# main.net
KiCad netlist of a schematic drawn in EAGLE
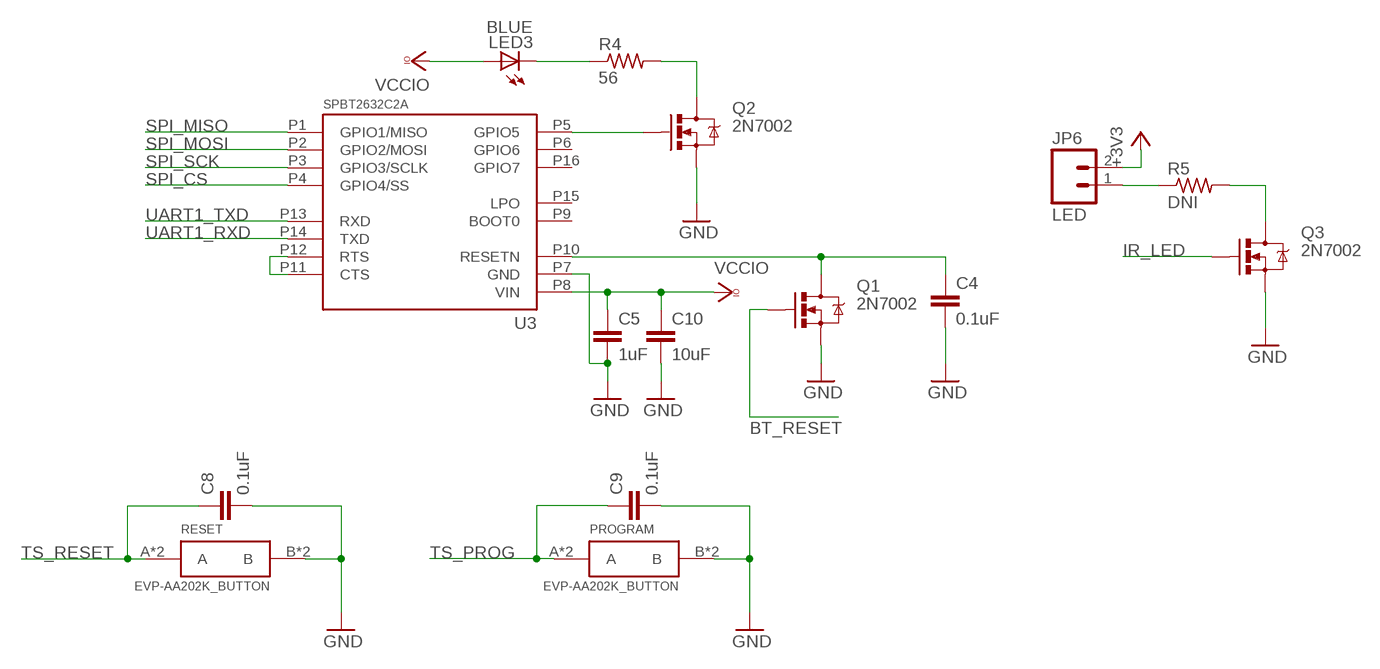
[diagram p0: schematic, sheet 1]
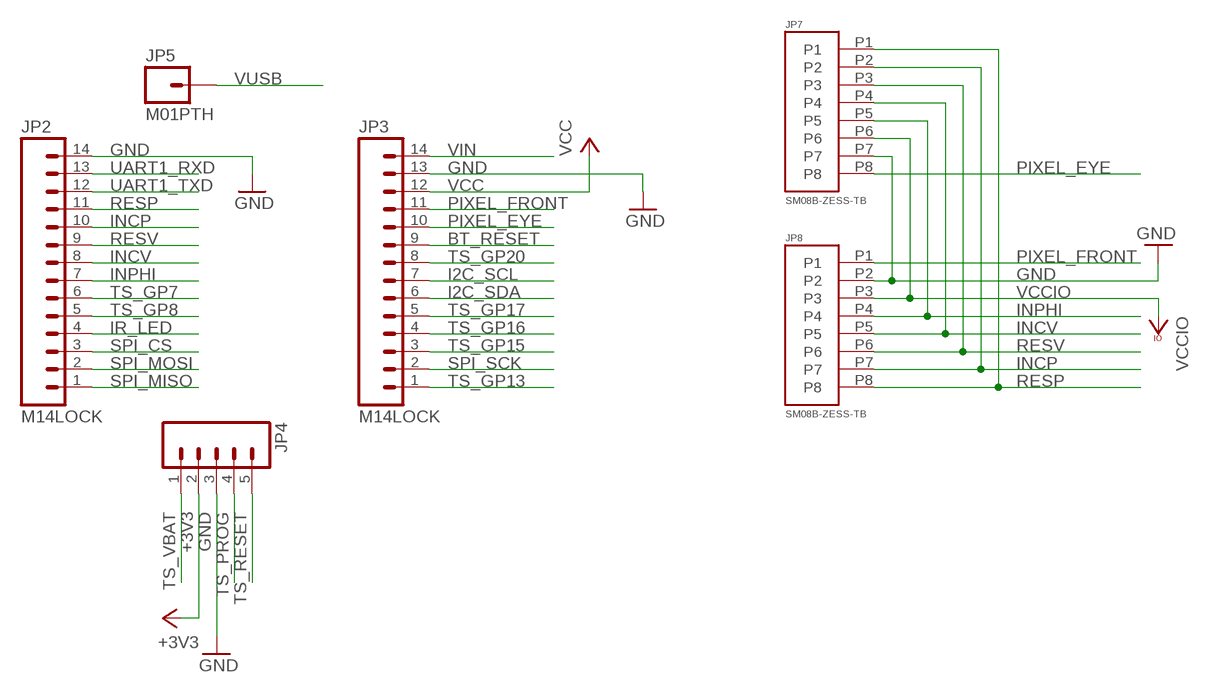
[diagram p1: schematic, sheet 2]
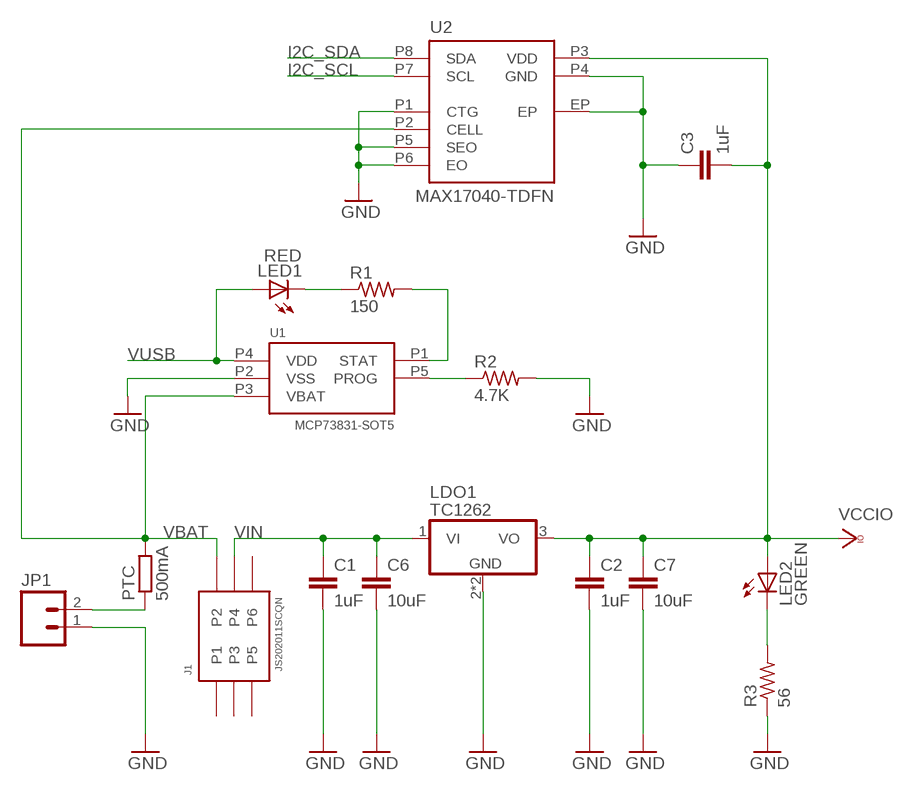
[diagram p2: schematic, sheet 3]

(export (version "E")
  (design (tool "Eeschema 10.0.6"))
  (components
    (comp (ref "JP2")
      (value "M14LOCK")
      (footprint "eagle-import:1X14_LOCK")
      (libsource (lib "eagle-import") (part "M14LOCK"))
    )
    (comp (ref "JP3")
      (value "M14LOCK")
      (footprint "eagle-import:1X14_LOCK")
      (libsource (lib "eagle-import") (part "M14LOCK"))
    )
    (comp (ref "JP4")
      (value "M05LOCK")
      (footprint "eagle-import:1X05_LOCK")
      (libsource (lib "eagle-import") (part "M05LOCK"))
    )
    (comp (ref "JP5")
      (value "M01PTH")
      (footprint "eagle-import:1X01")
      (libsource (lib "eagle-import") (part "M01PTH"))
    )
    (comp (ref "JP7")
      (value "SM08B-ZESS-TB")
      (footprint "eagle-import:SM08B_8PIN_SMD")
      (libsource (lib "eagle-import") (part "SM08B-ZESS-TB"))
    )
    (comp (ref "JP8")
      (value "SM08B-ZESS-TB")
      (footprint "eagle-import:SM08B_8PIN_SMD")
      (libsource (lib "eagle-import") (part "SM08B-ZESS-TB"))
    )
    (comp (ref "C1")
      (value "1uF")
      (footprint "eagle-import:C0402")
      (libsource (lib "eagle-import") (part "C-EUC0402"))
    )
    (comp (ref "C2")
      (value "1uF")
      (footprint "eagle-import:C0402")
      (libsource (lib "eagle-import") (part "C-EUC0402"))
    )
    (comp (ref "C3")
      (value "1uF")
      (footprint "eagle-import:C0402")
      (libsource (lib "eagle-import") (part "C-EUC0402"))
    )
    (comp (ref "C6")
      (value "10uF")
      (footprint "eagle-import:C0603")
      (libsource (lib "eagle-import") (part "C-EUC0603"))
    )
    (comp (ref "C7")
      (value "10uF")
      (footprint "eagle-import:C0603")
      (libsource (lib "eagle-import") (part "C-EUC0603"))
    )
    (comp (ref "J1")
      (value "JS202011SCQN")
      (footprint "eagle-import:JS2020_6PIN_SMT")
      (libsource (lib "eagle-import") (part "JS202011SCQN"))
    )
    (comp (ref "JP1")
      (value "M02-JST-2MM-SMT")
      (footprint "eagle-import:JST-2-SMD")
      (libsource (lib "eagle-import") (part "M02-JST-2MM-SMT"))
    )
    (comp (ref "LDO1")
      (value "TC1262")
      (footprint "eagle-import:SOT223")
      (libsource (lib "eagle-import") (part "MCP1703DB"))
    )
    (comp (ref "LED1")
      (value "RED")
      (footprint "eagle-import:CHIPLED_0603")
      (libsource (lib "eagle-import") (part "LEDCHIPLED_0603"))
    )
    (comp (ref "LED2")
      (value "GREEN")
      (footprint "eagle-import:CHIPLED_0603")
      (libsource (lib "eagle-import") (part "LEDCHIPLED_0603"))
    )
    (comp (ref "PTC")
      (value "500mA")
      (footprint "eagle-import:R0402")
      (libsource (lib "eagle-import") (part "R-EU_R0402"))
    )
    (comp (ref "R1")
      (value "150")
      (footprint "eagle-import:R0402")
      (libsource (lib "eagle-import") (part "R-US_R0402"))
    )
    (comp (ref "R2")
      (value "4.7K")
      (footprint "eagle-import:R0402")
      (libsource (lib "eagle-import") (part "R-US_R0402"))
    )
    (comp (ref "R3")
      (value "56")
      (footprint "eagle-import:R0402")
      (libsource (lib "eagle-import") (part "R-US_R0402"))
    )
    (comp (ref "U1")
      (value "MCP73831-SOT5")
      (footprint "eagle-import:SOT23-5")
      (libsource (lib "eagle-import") (part "MCP73831-SOT5"))
    )
    (comp (ref "U2")
      (value "MAX17040-TDFN")
      (footprint "eagle-import:TDFN_8PIN")
      (libsource (lib "eagle-import") (part "MAX17040-TDFN"))
    )
    (comp (ref "C4")
      (value "0.1uF")
      (footprint "eagle-import:C0402")
      (libsource (lib "eagle-import") (part "C-EUC0402"))
    )
    (comp (ref "C5")
      (value "1uF")
      (footprint "eagle-import:C0402")
      (libsource (lib "eagle-import") (part "C-EUC0402"))
    )
    (comp (ref "C8")
      (value "0.1uF")
      (footprint "eagle-import:C0402")
      (libsource (lib "eagle-import") (part "C-EUC0402"))
    )
    (comp (ref "C9")
      (value "0.1uF")
      (footprint "eagle-import:C0402")
      (libsource (lib "eagle-import") (part "C-EUC0402"))
    )
    (comp (ref "C10")
      (value "10uF")
      (footprint "eagle-import:C0603")
      (libsource (lib "eagle-import") (part "C-EUC0603"))
    )
    (comp (ref "JP6")
      (value "LED")
      (footprint "eagle-import:1X02_LOCK_LONGPADS")
      (libsource (lib "eagle-import") (part "M02LOCK_LONGPADS"))
    )
    (comp (ref "LED3")
      (value "BLUE")
      (footprint "eagle-import:CHIPLED_0603")
      (libsource (lib "eagle-import") (part "LEDCHIPLED_0603"))
    )
    (comp (ref "PROGRAM")
      (value "EVP-AA202K_BUTTON")
      (footprint "eagle-import:EVP-AA202K_4PIN")
      (libsource (lib "eagle-import") (part "EVP-AA202K_BUTTON"))
    )
    (comp (ref "Q1")
      (value "2N7002")
      (footprint "eagle-import:SOT23-3")
      (libsource (lib "eagle-import") (part "MOSFET-NCHANNELSMD"))
    )
    (comp (ref "Q2")
      (value "2N7002")
      (footprint "eagle-import:SOT23-3")
      (libsource (lib "eagle-import") (part "MOSFET-NCHANNELSMD"))
    )
    (comp (ref "Q3")
      (value "2N7002")
      (footprint "eagle-import:SOT23-3")
      (libsource (lib "eagle-import") (part "MOSFET-NCHANNELSMD"))
    )
    (comp (ref "R4")
      (value "56")
      (footprint "eagle-import:R0402")
      (libsource (lib "eagle-import") (part "R-US_R0402"))
    )
    (comp (ref "R5")
      (value "DNI")
      (footprint "eagle-import:R0402")
      (libsource (lib "eagle-import") (part "R-US_R0402"))
    )
    (comp (ref "RESET")
      (value "EVP-AA202K_BUTTON")
      (footprint "eagle-import:EVP-AA202K_4PIN")
      (libsource (lib "eagle-import") (part "EVP-AA202K_BUTTON"))
    )
    (comp (ref "U3")
      (value "SPBT2632C2A")
      (footprint "eagle-import:SPBT2632C2A_16PIN_SMD")
      (libsource (lib "eagle-import") (part "SPBT2632C2A"))
    )
  )
  (nets
    (net (code "1") (name "+3V3") (class "Default")
      (node (ref "JP4") (pin "2") (pinfunction "2_2") (pintype "passive"))
      (node (ref "JP6") (pin "2") (pinfunction "2_2") (pintype "passive"))
    )
    (net (code "2") (name "BT_RESET") (class "Default")
      (node (ref "JP3") (pin "9") (pinfunction "9_9") (pintype "passive"))
      (node (ref "Q1") (pin "1") (pinfunction "G_1") (pintype "passive"))
    )
    (net (code "3") (name "GND") (class "Default")
      (node (ref "C1") (pin "2") (pinfunction "2_2") (pintype "passive"))
      (node (ref "C10") (pin "2") (pinfunction "2_2") (pintype "passive"))
      (node (ref "C2") (pin "2") (pinfunction "2_2") (pintype "passive"))
      (node (ref "C3") (pin "1") (pinfunction "1_1") (pintype "passive"))
      (node (ref "C4") (pin "2") (pinfunction "2_2") (pintype "passive"))
      (node (ref "C5") (pin "2") (pinfunction "2_2") (pintype "passive"))
      (node (ref "C6") (pin "2") (pinfunction "2_2") (pintype "passive"))
      (node (ref "C7") (pin "2") (pinfunction "2_2") (pintype "passive"))
      (node (ref "C8") (pin "2") (pinfunction "2_2") (pintype "passive"))
      (node (ref "C9") (pin "2") (pinfunction "2_2") (pintype "passive"))
      (node (ref "JP1") (pin "1") (pinfunction "1_1") (pintype "passive"))
      (node (ref "JP2") (pin "14") (pinfunction "14_14") (pintype "passive"))
      (node (ref "JP3") (pin "13") (pinfunction "13_13") (pintype "passive"))
      (node (ref "JP4") (pin "3") (pinfunction "3_3") (pintype "passive"))
      (node (ref "JP7") (pin "P7") (pinfunction "P7_P7") (pintype "bidirectional"))
      (node (ref "JP8") (pin "P2") (pinfunction "P2_P2") (pintype "bidirectional"))
      (node (ref "LDO1") (pin "2") (pinfunction "GND_2") (pintype "passive"))
      (node (ref "LDO1") (pin "4") (pinfunction "GND_4") (pintype "passive"))
      (node (ref "PROGRAM") (pin "B") (pinfunction "B_B") (pintype "bidirectional"))
      (node (ref "PROGRAM") (pin "B'") (pinfunction "B_B'") (pintype "bidirectional"))
      (node (ref "Q1") (pin "2") (pinfunction "S_2") (pintype "passive"))
      (node (ref "Q2") (pin "2") (pinfunction "S_2") (pintype "passive"))
      (node (ref "Q3") (pin "2") (pinfunction "S_2") (pintype "passive"))
      (node (ref "R2") (pin "2") (pinfunction "2_2") (pintype "passive"))
      (node (ref "R3") (pin "1") (pinfunction "1_1") (pintype "passive"))
      (node (ref "RESET") (pin "B") (pinfunction "B_B") (pintype "bidirectional"))
      (node (ref "RESET") (pin "B'") (pinfunction "B_B'") (pintype "bidirectional"))
      (node (ref "U1") (pin "P2") (pinfunction "VSS_P2") (pintype "bidirectional"))
      (node (ref "U2") (pin "EP") (pinfunction "EP_EP") (pintype "bidirectional"))
      (node (ref "U2") (pin "P1") (pinfunction "CTG_P1") (pintype "bidirectional"))
      (node (ref "U2") (pin "P4") (pinfunction "GND_P4") (pintype "bidirectional"))
      (node (ref "U2") (pin "P5") (pinfunction "SEO_P5") (pintype "bidirectional"))
      (node (ref "U2") (pin "P6") (pinfunction "EO_P6") (pintype "bidirectional"))
      (node (ref "U3") (pin "P7") (pinfunction "GND_P7") (pintype "bidirectional"))
    )
    (net (code "4") (name "I2C_SCL") (class "Default")
      (node (ref "JP3") (pin "7") (pinfunction "7_7") (pintype "passive"))
      (node (ref "U2") (pin "P7") (pinfunction "SCL_P7") (pintype "bidirectional"))
    )
    (net (code "5") (name "I2C_SDA") (class "Default")
      (node (ref "JP3") (pin "6") (pinfunction "6_6") (pintype "passive"))
      (node (ref "U2") (pin "P8") (pinfunction "SDA_P8") (pintype "bidirectional"))
    )
    (net (code "6") (name "INCP") (class "Default")
      (node (ref "JP2") (pin "10") (pinfunction "10_10") (pintype "passive"))
      (node (ref "JP7") (pin "P2") (pinfunction "P2_P2") (pintype "bidirectional"))
      (node (ref "JP8") (pin "P7") (pinfunction "P7_P7") (pintype "bidirectional"))
    )
    (net (code "7") (name "INCV") (class "Default")
      (node (ref "JP2") (pin "8") (pinfunction "8_8") (pintype "passive"))
      (node (ref "JP7") (pin "P4") (pinfunction "P4_P4") (pintype "bidirectional"))
      (node (ref "JP8") (pin "P5") (pinfunction "P5_P5") (pintype "bidirectional"))
    )
    (net (code "8") (name "INPHI") (class "Default")
      (node (ref "JP2") (pin "7") (pinfunction "7_7") (pintype "passive"))
      (node (ref "JP7") (pin "P5") (pinfunction "P5_P5") (pintype "bidirectional"))
      (node (ref "JP8") (pin "P4") (pinfunction "P4_P4") (pintype "bidirectional"))
    )
    (net (code "9") (name "IR_LED") (class "Default")
      (node (ref "JP2") (pin "4") (pinfunction "4_4") (pintype "passive"))
      (node (ref "Q3") (pin "1") (pinfunction "G_1") (pintype "passive"))
    )
    (net (code "10") (name "Net-(JP1-Pad2)") (class "Default")
      (node (ref "JP1") (pin "2") (pinfunction "2_2") (pintype "passive"))
      (node (ref "PTC") (pin "1") (pinfunction "1_1") (pintype "passive"))
    )
    (net (code "11") (name "Net-(JP6-Pad1)") (class "Default")
      (node (ref "JP6") (pin "1") (pinfunction "1_1") (pintype "passive"))
      (node (ref "R5") (pin "1") (pinfunction "1_1") (pintype "passive"))
    )
    (net (code "12") (name "Net-(LED1-PadC)") (class "Default")
      (node (ref "LED1") (pin "C") (pinfunction "C_C") (pintype "passive"))
      (node (ref "R1") (pin "1") (pinfunction "1_1") (pintype "passive"))
    )
    (net (code "13") (name "Net-(LED2-PadC)") (class "Default")
      (node (ref "LED2") (pin "C") (pinfunction "C_C") (pintype "passive"))
      (node (ref "R3") (pin "2") (pinfunction "2_2") (pintype "passive"))
    )
    (net (code "14") (name "Net-(LED3-PadC)") (class "Default")
      (node (ref "LED3") (pin "C") (pinfunction "C_C") (pintype "passive"))
      (node (ref "R4") (pin "1") (pinfunction "1_1") (pintype "passive"))
    )
    (net (code "15") (name "Net-(Q1-D)") (class "Default")
      (node (ref "C4") (pin "1") (pinfunction "1_1") (pintype "passive"))
      (node (ref "Q1") (pin "3") (pinfunction "D_3") (pintype "passive"))
      (node (ref "U3") (pin "P10") (pinfunction "RESETN_P10") (pintype "bidirectional"))
    )
    (net (code "16") (name "Net-(Q2-D)") (class "Default")
      (node (ref "Q2") (pin "3") (pinfunction "D_3") (pintype "passive"))
      (node (ref "R4") (pin "2") (pinfunction "2_2") (pintype "passive"))
    )
    (net (code "17") (name "Net-(Q2-G)") (class "Default")
      (node (ref "Q2") (pin "1") (pinfunction "G_1") (pintype "passive"))
      (node (ref "U3") (pin "P5") (pinfunction "GPIO5_P5") (pintype "bidirectional"))
    )
    (net (code "18") (name "Net-(Q3-D)") (class "Default")
      (node (ref "Q3") (pin "3") (pinfunction "D_3") (pintype "passive"))
      (node (ref "R5") (pin "2") (pinfunction "2_2") (pintype "passive"))
    )
    (net (code "19") (name "Net-(U1-PROG)") (class "Default")
      (node (ref "R2") (pin "1") (pinfunction "1_1") (pintype "passive"))
      (node (ref "U1") (pin "P5") (pinfunction "PROG_P5") (pintype "bidirectional"))
    )
    (net (code "20") (name "Net-(U1-STAT)") (class "Default")
      (node (ref "R1") (pin "2") (pinfunction "2_2") (pintype "passive"))
      (node (ref "U1") (pin "P1") (pinfunction "STAT_P1") (pintype "bidirectional"))
    )
    (net (code "21") (name "Net-(U3-CTS)") (class "Default")
      (node (ref "U3") (pin "P11") (pinfunction "CTS_P11") (pintype "bidirectional"))
      (node (ref "U3") (pin "P12") (pinfunction "RTS_P12") (pintype "bidirectional"))
    )
    (net (code "22") (name "PIXEL_EYE") (class "Default")
      (node (ref "JP3") (pin "10") (pinfunction "10_10") (pintype "passive"))
      (node (ref "JP7") (pin "P8") (pinfunction "P8_P8") (pintype "bidirectional"))
    )
    (net (code "23") (name "PIXEL_FRONT") (class "Default")
      (node (ref "JP3") (pin "11") (pinfunction "11_11") (pintype "passive"))
      (node (ref "JP8") (pin "P1") (pinfunction "P1_P1") (pintype "bidirectional"))
    )
    (net (code "24") (name "RESP") (class "Default")
      (node (ref "JP2") (pin "11") (pinfunction "11_11") (pintype "passive"))
      (node (ref "JP7") (pin "P1") (pinfunction "P1_P1") (pintype "bidirectional"))
      (node (ref "JP8") (pin "P8") (pinfunction "P8_P8") (pintype "bidirectional"))
    )
    (net (code "25") (name "RESV") (class "Default")
      (node (ref "JP2") (pin "9") (pinfunction "9_9") (pintype "passive"))
      (node (ref "JP7") (pin "P3") (pinfunction "P3_P3") (pintype "bidirectional"))
      (node (ref "JP8") (pin "P6") (pinfunction "P6_P6") (pintype "bidirectional"))
    )
    (net (code "26") (name "SPI_CS") (class "Default")
      (node (ref "JP2") (pin "3") (pinfunction "3_3") (pintype "passive"))
      (node (ref "U3") (pin "P4") (pinfunction "GPIO4/SS_P4") (pintype "bidirectional"))
    )
    (net (code "27") (name "SPI_MISO") (class "Default")
      (node (ref "JP2") (pin "1") (pinfunction "1_1") (pintype "passive"))
      (node (ref "U3") (pin "P1") (pinfunction "GPIO1/MISO_P1") (pintype "bidirectional"))
    )
    (net (code "28") (name "SPI_MOSI") (class "Default")
      (node (ref "JP2") (pin "2") (pinfunction "2_2") (pintype "passive"))
      (node (ref "U3") (pin "P2") (pinfunction "GPIO2/MOSI_P2") (pintype "bidirectional"))
    )
    (net (code "29") (name "SPI_SCK") (class "Default")
      (node (ref "JP3") (pin "2") (pinfunction "2_2") (pintype "passive"))
      (node (ref "U3") (pin "P3") (pinfunction "GPIO3/SCLK_P3") (pintype "bidirectional"))
    )
    (net (code "30") (name "TS_GP7") (class "Default")
      (node (ref "JP2") (pin "6") (pinfunction "6_6") (pintype "passive"))
    )
    (net (code "31") (name "TS_GP8") (class "Default")
      (node (ref "JP2") (pin "5") (pinfunction "5_5") (pintype "passive"))
    )
    (net (code "32") (name "TS_GP13") (class "Default")
      (node (ref "JP3") (pin "1") (pinfunction "1_1") (pintype "passive"))
    )
    (net (code "33") (name "TS_GP15") (class "Default")
      (node (ref "JP3") (pin "3") (pinfunction "3_3") (pintype "passive"))
    )
    (net (code "34") (name "TS_GP16") (class "Default")
      (node (ref "JP3") (pin "4") (pinfunction "4_4") (pintype "passive"))
    )
    (net (code "35") (name "TS_GP17") (class "Default")
      (node (ref "JP3") (pin "5") (pinfunction "5_5") (pintype "passive"))
    )
    (net (code "36") (name "TS_GP20") (class "Default")
      (node (ref "JP3") (pin "8") (pinfunction "8_8") (pintype "passive"))
    )
    (net (code "37") (name "TS_PROG") (class "Default")
      (node (ref "C9") (pin "1") (pinfunction "1_1") (pintype "passive"))
      (node (ref "JP4") (pin "4") (pinfunction "4_4") (pintype "passive"))
      (node (ref "PROGRAM") (pin "A") (pinfunction "A_A") (pintype "bidirectional"))
      (node (ref "PROGRAM") (pin "A'") (pinfunction "A_A'") (pintype "bidirectional"))
    )
    (net (code "38") (name "TS_RESET") (class "Default")
      (node (ref "C8") (pin "1") (pinfunction "1_1") (pintype "passive"))
      (node (ref "JP4") (pin "5") (pinfunction "5_5") (pintype "passive"))
      (node (ref "RESET") (pin "A") (pinfunction "A_A") (pintype "bidirectional"))
      (node (ref "RESET") (pin "A'") (pinfunction "A_A'") (pintype "bidirectional"))
    )
    (net (code "39") (name "TS_VBAT") (class "Default")
      (node (ref "JP4") (pin "1") (pinfunction "1_1") (pintype "passive"))
    )
    (net (code "40") (name "UART1_RXD") (class "Default")
      (node (ref "JP2") (pin "13") (pinfunction "13_13") (pintype "passive"))
      (node (ref "U3") (pin "P14") (pinfunction "TXD_P14") (pintype "bidirectional"))
    )
    (net (code "41") (name "UART1_TXD") (class "Default")
      (node (ref "JP2") (pin "12") (pinfunction "12_12") (pintype "passive"))
      (node (ref "U3") (pin "P13") (pinfunction "RXD_P13") (pintype "bidirectional"))
    )
    (net (code "42") (name "VBAT") (class "Default")
      (node (ref "J1") (pin "P2") (pinfunction "P2_P2") (pintype "bidirectional"))
      (node (ref "PTC") (pin "2") (pinfunction "2_2") (pintype "passive"))
      (node (ref "U1") (pin "P3") (pinfunction "VBAT_P3") (pintype "bidirectional"))
      (node (ref "U2") (pin "P2") (pinfunction "CELL_P2") (pintype "bidirectional"))
    )
    (net (code "43") (name "VCC") (class "Default")
      (node (ref "JP3") (pin "12") (pinfunction "12_12") (pintype "passive"))
    )
    (net (code "44") (name "VCCIO") (class "Default")
      (node (ref "C10") (pin "1") (pinfunction "1_1") (pintype "passive"))
      (node (ref "C2") (pin "1") (pinfunction "1_1") (pintype "passive"))
      (node (ref "C3") (pin "2") (pinfunction "2_2") (pintype "passive"))
      (node (ref "C5") (pin "1") (pinfunction "1_1") (pintype "passive"))
      (node (ref "C7") (pin "1") (pinfunction "1_1") (pintype "passive"))
      (node (ref "JP7") (pin "P6") (pinfunction "P6_P6") (pintype "bidirectional"))
      (node (ref "JP8") (pin "P3") (pinfunction "P3_P3") (pintype "bidirectional"))
      (node (ref "LDO1") (pin "3") (pinfunction "VO_3") (pintype "passive"))
      (node (ref "LED2") (pin "A") (pinfunction "A_A") (pintype "passive"))
      (node (ref "LED3") (pin "A") (pinfunction "A_A") (pintype "passive"))
      (node (ref "U2") (pin "P3") (pinfunction "VDD_P3") (pintype "bidirectional"))
      (node (ref "U3") (pin "P8") (pinfunction "VIN_P8") (pintype "bidirectional"))
    )
    (net (code "45") (name "VIN") (class "Default")
      (node (ref "C1") (pin "1") (pinfunction "1_1") (pintype "passive"))
      (node (ref "C6") (pin "1") (pinfunction "1_1") (pintype "passive"))
      (node (ref "J1") (pin "P4") (pinfunction "P4_P4") (pintype "bidirectional"))
      (node (ref "JP3") (pin "14") (pinfunction "14_14") (pintype "passive"))
      (node (ref "LDO1") (pin "1") (pinfunction "VI_1") (pintype "input"))
    )
    (net (code "46") (name "VUSB") (class "Default")
      (node (ref "JP5") (pin "1") (pinfunction "1_1") (pintype "passive"))
      (node (ref "LED1") (pin "A") (pinfunction "A_A") (pintype "passive"))
      (node (ref "U1") (pin "P4") (pinfunction "VDD_P4") (pintype "bidirectional"))
    )
    (net (code "47") (name "unconnected-(J1-PadP1)") (class "Default")
      (node (ref "J1") (pin "P1") (pinfunction "P1_P1") (pintype "bidirectional"))
    )
    (net (code "48") (name "unconnected-(J1-PadP3)") (class "Default")
      (node (ref "J1") (pin "P3") (pinfunction "P3_P3") (pintype "bidirectional"))
    )
    (net (code "49") (name "unconnected-(J1-PadP5)") (class "Default")
      (node (ref "J1") (pin "P5") (pinfunction "P5_P5") (pintype "bidirectional"))
    )
    (net (code "50") (name "unconnected-(J1-PadP6)") (class "Default")
      (node (ref "J1") (pin "P6") (pinfunction "P6_P6") (pintype "bidirectional"))
    )
    (net (code "51") (name "unconnected-(U3-BOOT0-PadP9)") (class "Default")
      (node (ref "U3") (pin "P9") (pinfunction "BOOT0_P9") (pintype "bidirectional"))
    )
    (net (code "52") (name "unconnected-(U3-GPIO6-PadP6)") (class "Default")
      (node (ref "U3") (pin "P6") (pinfunction "GPIO6_P6") (pintype "bidirectional"))
    )
    (net (code "53") (name "unconnected-(U3-GPIO7-PadP16)") (class "Default")
      (node (ref "U3") (pin "P16") (pinfunction "GPIO7_P16") (pintype "bidirectional"))
    )
    (net (code "54") (name "unconnected-(U3-LPO-PadP15)") (class "Default")
      (node (ref "U3") (pin "P15") (pinfunction "LPO_P15") (pintype "bidirectional"))
    )
  )
)
